# ESC_BOARD.net
KiCad netlist of a schematic drawn in EAGLE
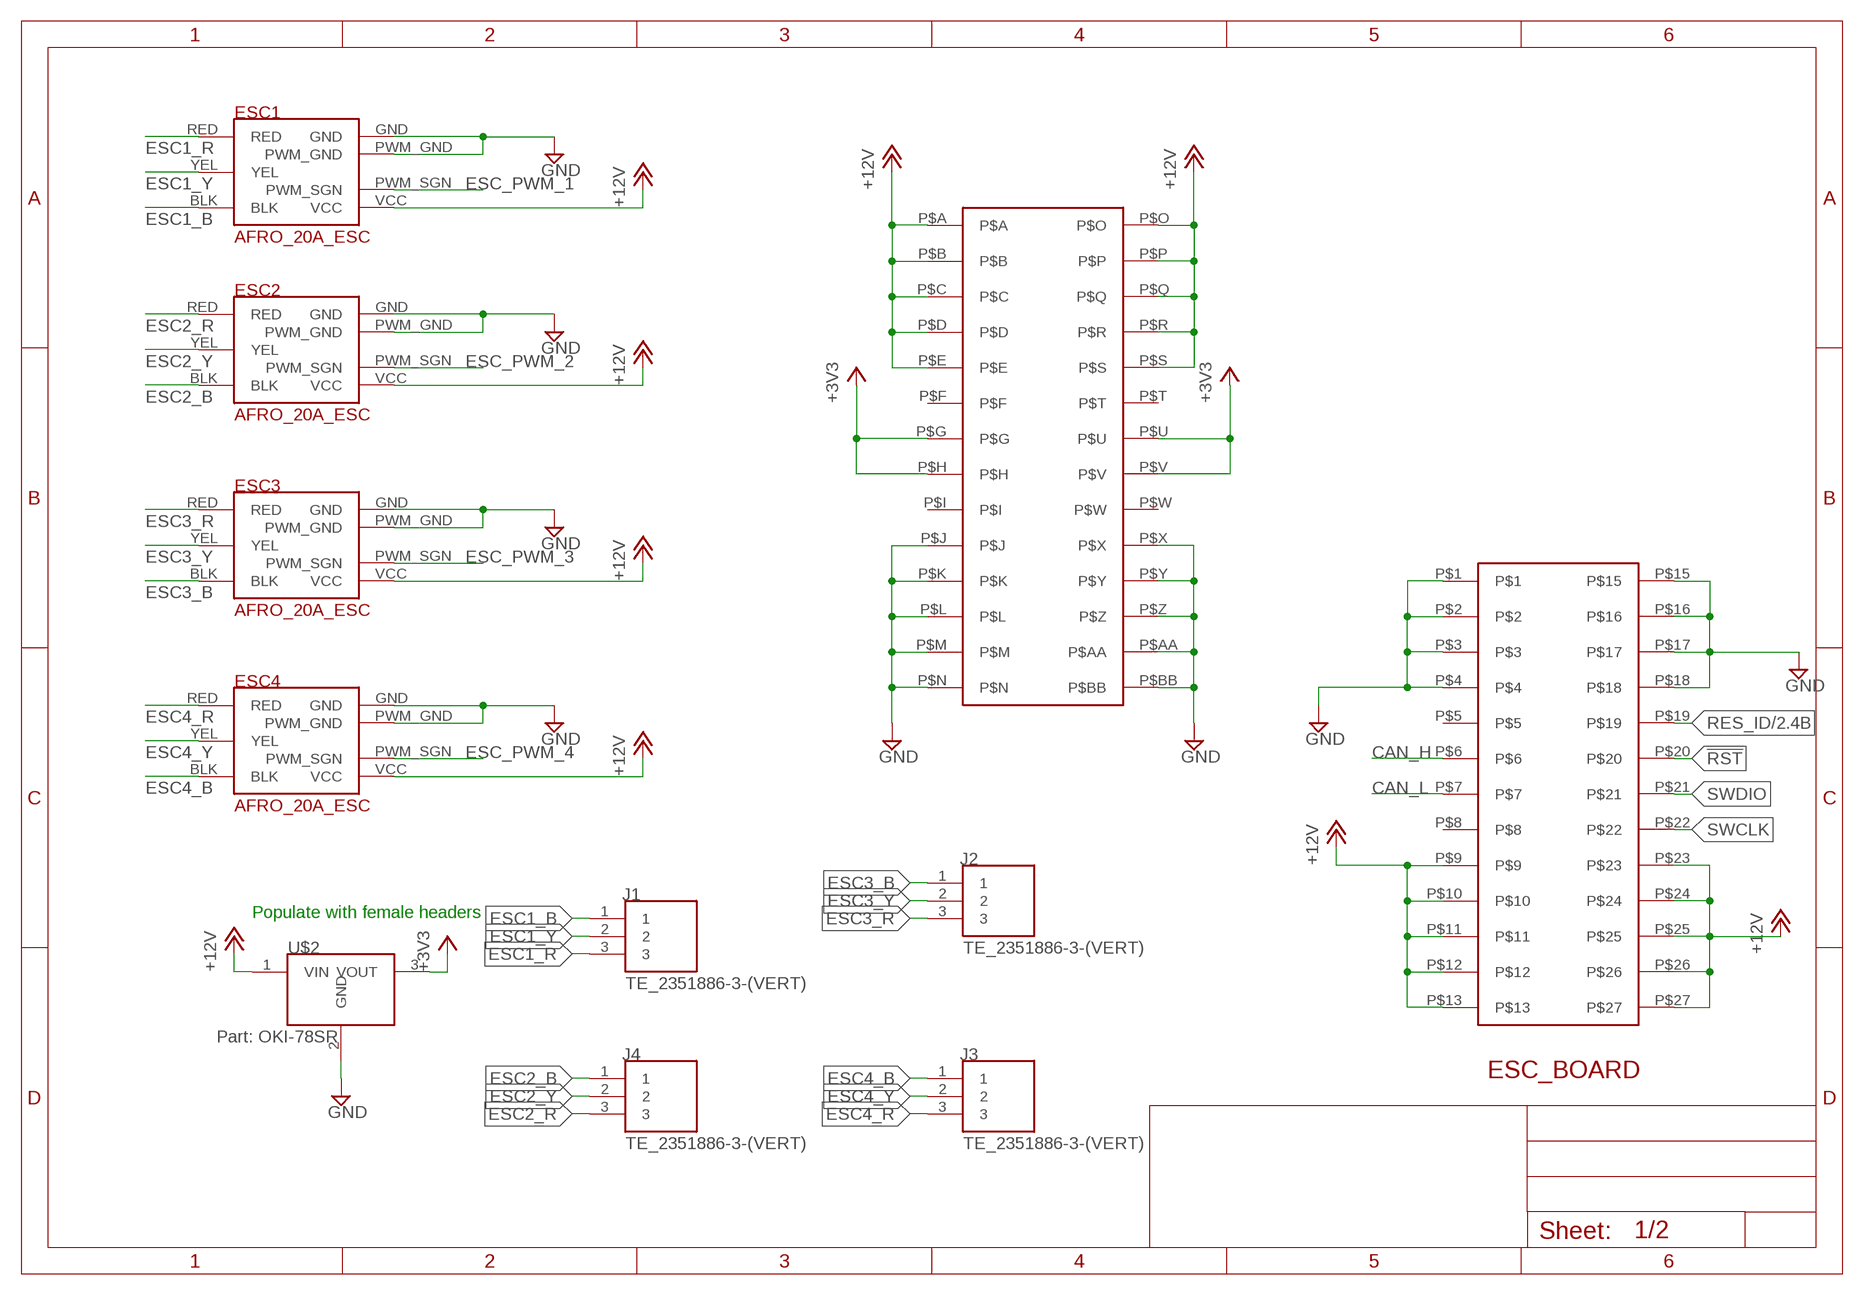
[diagram p0: schematic, sheet 1]
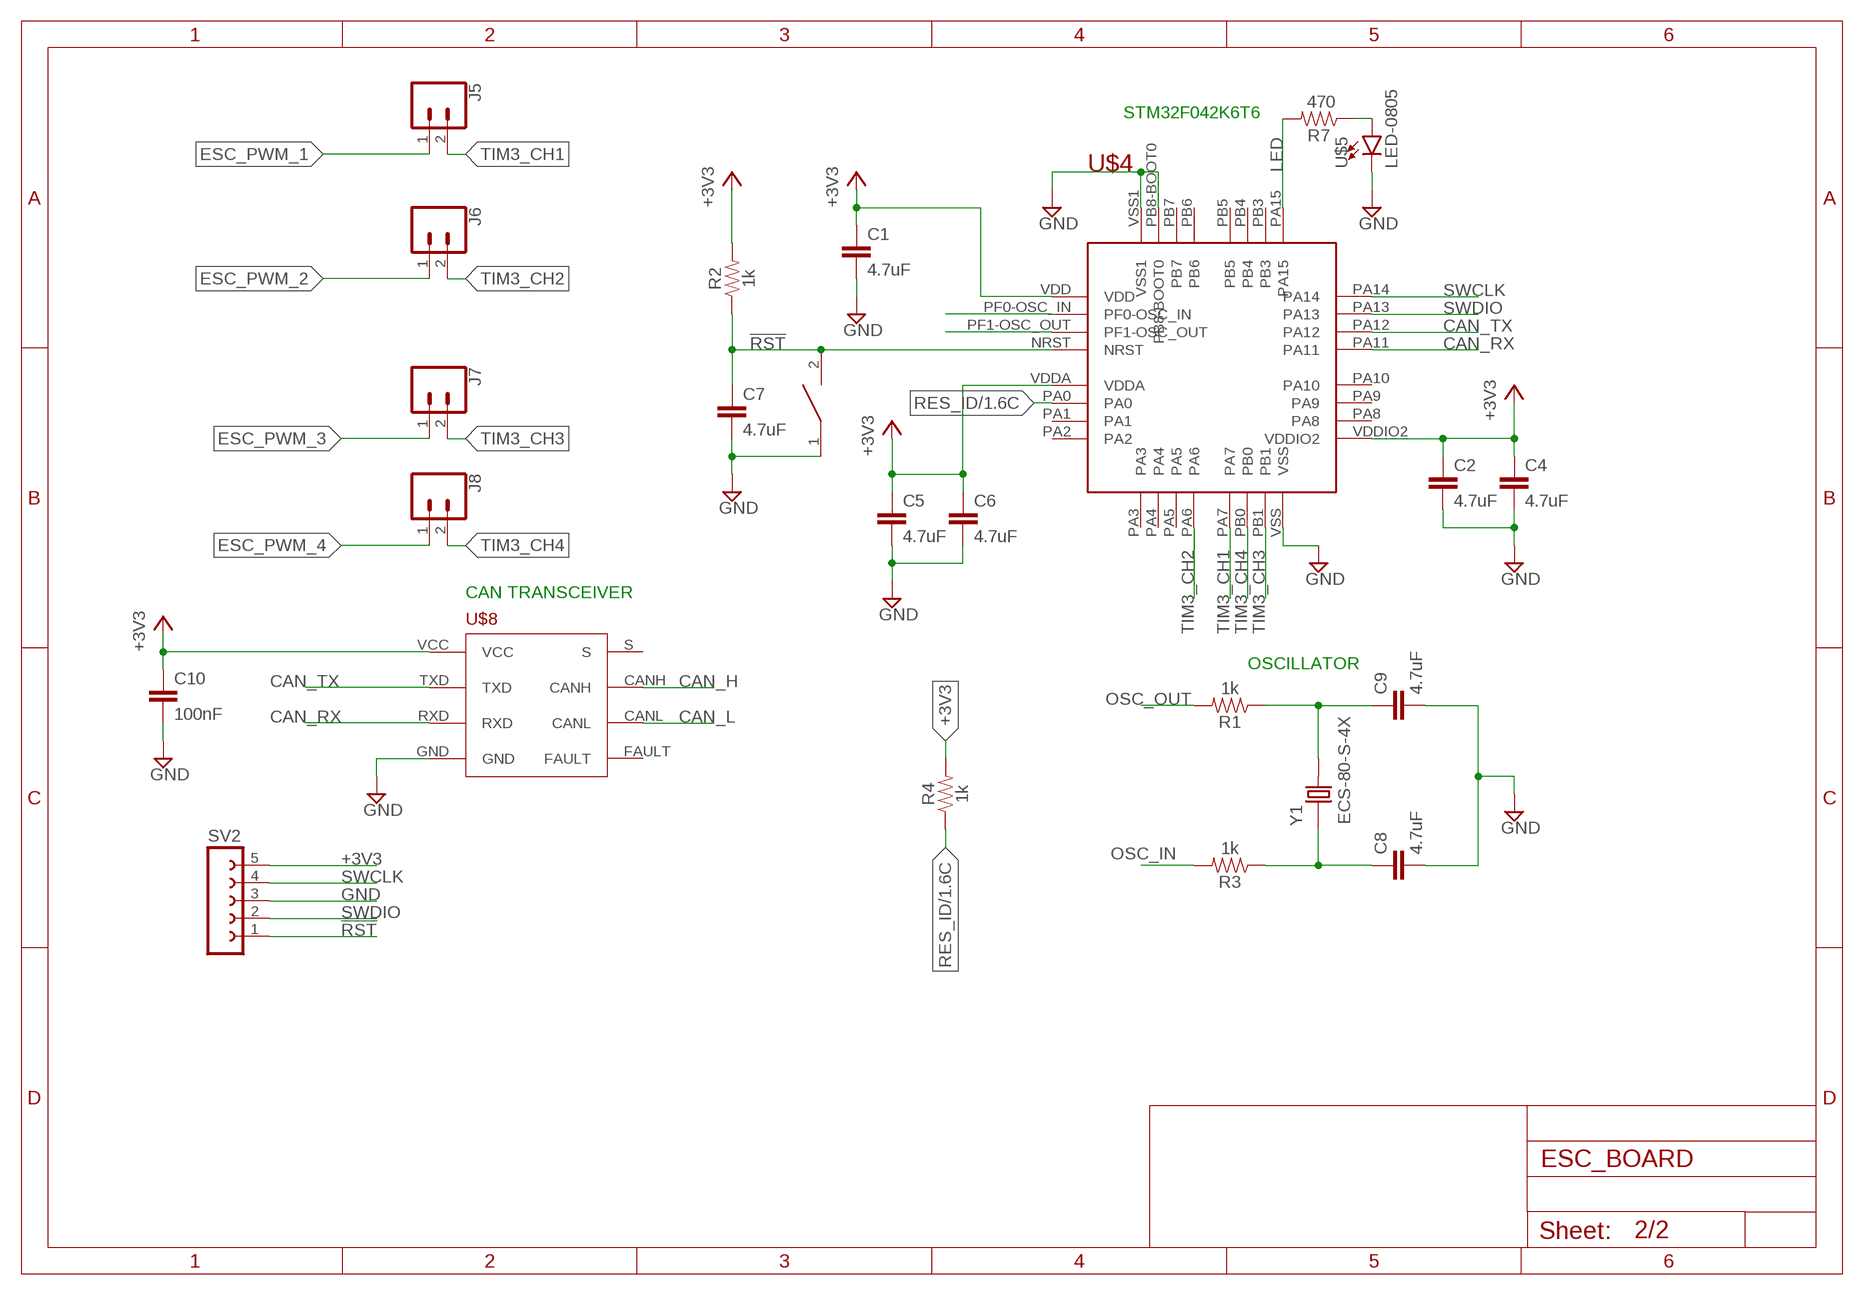
[diagram p1: schematic, sheet 2]

(export (version "E")
  (design (tool "Eeschema 10.0.6"))
  (components
    (comp (ref "C1")
      (value "4.7uF")
      (footprint "eagle-import:0603")
      (libsource (lib "eagle-import") (part "4.7UF0603"))
    )
    (comp (ref "C2")
      (value "4.7uF")
      (footprint "eagle-import:0603")
      (libsource (lib "eagle-import") (part "4.7UF0603"))
    )
    (comp (ref "C4")
      (value "4.7uF")
      (footprint "eagle-import:0603")
      (libsource (lib "eagle-import") (part "4.7UF0603"))
    )
    (comp (ref "C5")
      (value "4.7uF")
      (footprint "eagle-import:0603")
      (libsource (lib "eagle-import") (part "4.7UF0603"))
    )
    (comp (ref "C6")
      (value "4.7uF")
      (footprint "eagle-import:0603")
      (libsource (lib "eagle-import") (part "4.7UF0603"))
    )
    (comp (ref "C7")
      (value "4.7uF")
      (footprint "eagle-import:0603")
      (libsource (lib "eagle-import") (part "4.7UF0603"))
    )
    (comp (ref "C8")
      (value "4.7uF")
      (footprint "eagle-import:0603")
      (libsource (lib "eagle-import") (part "4.7UF0603"))
    )
    (comp (ref "C9")
      (value "4.7uF")
      (footprint "eagle-import:0603")
      (libsource (lib "eagle-import") (part "4.7UF0603"))
    )
    (comp (ref "C10")
      (value "100nF")
      (footprint "eagle-import:0603")
      (libsource (lib "eagle-import") (part "4.7UF0603"))
    )
    (comp (ref "J5")
      (value "CONN_02")
      (footprint "eagle-import:1X02")
      (libsource (lib "eagle-import") (part "CONN_02"))
    )
    (comp (ref "J6")
      (value "CONN_02")
      (footprint "eagle-import:1X02")
      (libsource (lib "eagle-import") (part "CONN_02"))
    )
    (comp (ref "J7")
      (value "CONN_02")
      (footprint "eagle-import:1X02")
      (libsource (lib "eagle-import") (part "CONN_02"))
    )
    (comp (ref "J8")
      (value "CONN_02")
      (footprint "eagle-import:1X02")
      (libsource (lib "eagle-import") (part "CONN_02"))
    )
    (comp (ref "R1")
      (value "1k")
      (footprint "eagle-import:0603")
      (libsource (lib "eagle-import") (part "1KOHM-0603-1/10W-1%"))
    )
    (comp (ref "R2")
      (value "1k")
      (footprint "eagle-import:0603")
      (libsource (lib "eagle-import") (part "1KOHM-0603-1/10W-1%"))
    )
    (comp (ref "R3")
      (value "1k")
      (footprint "eagle-import:0603")
      (libsource (lib "eagle-import") (part "1KOHM-0603-1/10W-1%"))
    )
    (comp (ref "R4")
      (value "1k")
      (footprint "eagle-import:0603")
      (libsource (lib "eagle-import") (part "1KOHM-0603-1/10W-1%"))
    )
    (comp (ref "R7")
      (value "470")
      (footprint "eagle-import:0603")
      (libsource (lib "eagle-import") (part "RESISTOR0603"))
    )
    (comp (ref "SV2")
      (value "FE05-1")
      (footprint "eagle-import:FE05-1")
      (libsource (lib "eagle-import") (part "FE05-1"))
    )
    (comp (ref "U$3")
      (value "DISCRETECOMPONENTS_SWITCH")
      (footprint "eagle-import:DISCRETECOMPONENTS_SW_2512")
      (libsource (lib "eagle-import") (part "DISCRETECOMPONENTS_SWITCH"))
    )
    (comp (ref "U$4")
      (value "STM32F042K6T6")
      (footprint "eagle-import:STM32F042K6T6")
      (libsource (lib "eagle-import") (part "STM32F042K6T6"))
    )
    (comp (ref "U$5")
      (value "LED-0805")
      (footprint "eagle-import:0805")
      (libsource (lib "eagle-import") (part "LED-0805"))
    )
    (comp (ref "U$8")
      (value "TCAN337D")
      (footprint "eagle-import:TCAN337D")
      (libsource (lib "eagle-import") (part "TCAN337D"))
    )
    (comp (ref "Y1")
      (value "ECS-80-S-4X")
      (footprint "eagle-import:XTAL_ECS-80-S-4X")
      (fields (field (name "DIGI-KEY_PART_NUMBER") "X1057-ND") (field (name "MF") "ECS International"))
      (libsource (lib "eagle-import") (part "ECS-80-S-4X"))
    )
    (comp (ref "ESC1")
      (value "AFRO_20A_ESC")
      (footprint "eagle-import:AFRO_20A_ESC")
      (libsource (lib "eagle-import") (part "AFRO_20A_ESC"))
    )
    (comp (ref "ESC2")
      (value "AFRO_20A_ESC")
      (footprint "eagle-import:AFRO_20A_ESC")
      (libsource (lib "eagle-import") (part "AFRO_20A_ESC"))
    )
    (comp (ref "ESC3")
      (value "AFRO_20A_ESC")
      (footprint "eagle-import:AFRO_20A_ESC")
      (libsource (lib "eagle-import") (part "AFRO_20A_ESC"))
    )
    (comp (ref "ESC4")
      (value "AFRO_20A_ESC")
      (footprint "eagle-import:AFRO_20A_ESC")
      (libsource (lib "eagle-import") (part "AFRO_20A_ESC"))
    )
    (comp (ref "J1")
      (value "TE_2351886-3-(VERT)")
      (footprint "eagle-import:TE_2351886-3-(VERT)")
      (libsource (lib "eagle-import") (part "TE_2351886-3-(VERT)"))
    )
    (comp (ref "J2")
      (value "TE_2351886-3-(VERT)")
      (footprint "eagle-import:TE_2351886-3-(VERT)")
      (libsource (lib "eagle-import") (part "TE_2351886-3-(VERT)"))
    )
    (comp (ref "J3")
      (value "TE_2351886-3-(VERT)")
      (footprint "eagle-import:TE_2351886-3-(VERT)")
      (libsource (lib "eagle-import") (part "TE_2351886-3-(VERT)"))
    )
    (comp (ref "J4")
      (value "TE_2351886-3-(VERT)")
      (footprint "eagle-import:TE_2351886-3-(VERT)")
      (libsource (lib "eagle-import") (part "TE_2351886-3-(VERT)"))
    )
    (comp (ref "U$2")
      (value "MURATA-DC-DC")
      (footprint "eagle-import:MURATA-DC-DC")
      (libsource (lib "eagle-import") (part "MURATA-DC-DC"))
    )
    (comp (ref "U$6")
      (value "ESC2BACKPLANE")
      (footprint "eagle-import:ESC2BACKPLANE_WHOLE")
      (libsource (lib "eagle-import") (part "ESC2BACKPLANE"))
    )
  )
  (nets
    (net (code "1") (name "+3V3") (class "Default")
      (node (ref "C1") (pin "1") (pinfunction "1_1") (pintype "passive"))
      (node (ref "C10") (pin "1") (pinfunction "1_1") (pintype "passive"))
      (node (ref "C2") (pin "1") (pinfunction "1_1") (pintype "passive"))
      (node (ref "C4") (pin "1") (pinfunction "1_1") (pintype "passive"))
      (node (ref "C5") (pin "1") (pinfunction "1_1") (pintype "passive"))
      (node (ref "C6") (pin "1") (pinfunction "1_1") (pintype "passive"))
      (node (ref "R2") (pin "2") (pinfunction "2_2") (pintype "passive"))
      (node (ref "R4") (pin "2") (pinfunction "2_2") (pintype "passive"))
      (node (ref "SV2") (pin "5") (pinfunction "5_5") (pintype "passive"))
      (node (ref "U$2") (pin "3") (pinfunction "VOUT_3") (pintype "bidirectional"))
      (node (ref "U$4") (pin "VDD") (pinfunction "VDD_VDD") (pintype "bidirectional"))
      (node (ref "U$4") (pin "VDDA") (pinfunction "VDDA_VDDA") (pintype "bidirectional"))
      (node (ref "U$4") (pin "VDDIO2") (pinfunction "VDDIO2_VDDIO2") (pintype "bidirectional"))
      (node (ref "U$6") (pin "P$G") (pinfunction "P$G_P$G") (pintype "bidirectional"))
      (node (ref "U$6") (pin "P$H") (pinfunction "P$H_P$H") (pintype "bidirectional"))
      (node (ref "U$6") (pin "P$U") (pinfunction "P$U_P$U") (pintype "bidirectional"))
      (node (ref "U$6") (pin "P$V") (pinfunction "P$V_P$V") (pintype "bidirectional"))
      (node (ref "U$8") (pin "VCC") (pinfunction "VCC_VCC") (pintype "bidirectional"))
    )
    (net (code "2") (name "+12V") (class "Default")
      (node (ref "ESC1") (pin "VCC") (pinfunction "VCC_VCC") (pintype "bidirectional"))
      (node (ref "ESC2") (pin "VCC") (pinfunction "VCC_VCC") (pintype "bidirectional"))
      (node (ref "ESC3") (pin "VCC") (pinfunction "VCC_VCC") (pintype "bidirectional"))
      (node (ref "ESC4") (pin "VCC") (pinfunction "VCC_VCC") (pintype "bidirectional"))
      (node (ref "U$2") (pin "1") (pinfunction "VIN_1") (pintype "bidirectional"))
      (node (ref "U$6") (pin "P$10") (pinfunction "P$10_P$10") (pintype "bidirectional"))
      (node (ref "U$6") (pin "P$11") (pinfunction "P$11_P$11") (pintype "bidirectional"))
      (node (ref "U$6") (pin "P$12") (pinfunction "P$12_P$12") (pintype "bidirectional"))
      (node (ref "U$6") (pin "P$13") (pinfunction "P$13_P$13") (pintype "bidirectional"))
      (node (ref "U$6") (pin "P$23") (pinfunction "P$23_P$23") (pintype "bidirectional"))
      (node (ref "U$6") (pin "P$24") (pinfunction "P$24_P$24") (pintype "bidirectional"))
      (node (ref "U$6") (pin "P$25") (pinfunction "P$25_P$25") (pintype "bidirectional"))
      (node (ref "U$6") (pin "P$26") (pinfunction "P$26_P$26") (pintype "bidirectional"))
      (node (ref "U$6") (pin "P$27") (pinfunction "P$27_P$27") (pintype "bidirectional"))
      (node (ref "U$6") (pin "P$9") (pinfunction "P$9_P$9") (pintype "bidirectional"))
      (node (ref "U$6") (pin "P$A") (pinfunction "P$A_P$A") (pintype "bidirectional"))
      (node (ref "U$6") (pin "P$B") (pinfunction "P$B_P$B") (pintype "bidirectional"))
      (node (ref "U$6") (pin "P$C") (pinfunction "P$C_P$C") (pintype "bidirectional"))
      (node (ref "U$6") (pin "P$D") (pinfunction "P$D_P$D") (pintype "bidirectional"))
      (node (ref "U$6") (pin "P$E") (pinfunction "P$E_P$E") (pintype "bidirectional"))
      (node (ref "U$6") (pin "P$O") (pinfunction "P$O_P$O") (pintype "bidirectional"))
      (node (ref "U$6") (pin "P$P") (pinfunction "P$P_P$P") (pintype "bidirectional"))
      (node (ref "U$6") (pin "P$Q") (pinfunction "P$Q_P$Q") (pintype "bidirectional"))
      (node (ref "U$6") (pin "P$R") (pinfunction "P$R_P$R") (pintype "bidirectional"))
      (node (ref "U$6") (pin "P$S") (pinfunction "P$S_P$S") (pintype "bidirectional"))
    )
    (net (code "3") (name "CAN_H") (class "Default")
      (node (ref "U$6") (pin "P$6") (pinfunction "P$6_P$6") (pintype "bidirectional"))
      (node (ref "U$8") (pin "CANH") (pinfunction "CANH_CANH") (pintype "bidirectional"))
    )
    (net (code "4") (name "CAN_L") (class "Default")
      (node (ref "U$6") (pin "P$7") (pinfunction "P$7_P$7") (pintype "bidirectional"))
      (node (ref "U$8") (pin "CANL") (pinfunction "CANL_CANL") (pintype "bidirectional"))
    )
    (net (code "5") (name "CAN_RX") (class "Default")
      (node (ref "U$4") (pin "PA11") (pinfunction "PA11_PA11") (pintype "bidirectional"))
      (node (ref "U$8") (pin "RXD") (pinfunction "RXD_RXD") (pintype "bidirectional"))
    )
    (net (code "6") (name "CAN_TX") (class "Default")
      (node (ref "U$4") (pin "PA12") (pinfunction "PA12_PA12") (pintype "bidirectional"))
      (node (ref "U$8") (pin "TXD") (pinfunction "TXD_TXD") (pintype "bidirectional"))
    )
    (net (code "7") (name "ESC1_B") (class "Default")
      (node (ref "ESC1") (pin "BLK") (pinfunction "BLK_BLK") (pintype "bidirectional"))
      (node (ref "J1") (pin "1") (pinfunction "1_1") (pintype "passive"))
    )
    (net (code "8") (name "ESC1_R") (class "Default")
      (node (ref "ESC1") (pin "RED") (pinfunction "RED_RED") (pintype "bidirectional"))
      (node (ref "J1") (pin "3") (pinfunction "3_3") (pintype "passive"))
    )
    (net (code "9") (name "ESC1_Y") (class "Default")
      (node (ref "ESC1") (pin "YEL") (pinfunction "YEL_YEL") (pintype "bidirectional"))
      (node (ref "J1") (pin "2") (pinfunction "2_2") (pintype "passive"))
    )
    (net (code "10") (name "ESC2_B") (class "Default")
      (node (ref "ESC2") (pin "BLK") (pinfunction "BLK_BLK") (pintype "bidirectional"))
      (node (ref "J4") (pin "1") (pinfunction "1_1") (pintype "passive"))
    )
    (net (code "11") (name "ESC2_R") (class "Default")
      (node (ref "ESC2") (pin "RED") (pinfunction "RED_RED") (pintype "bidirectional"))
      (node (ref "J4") (pin "3") (pinfunction "3_3") (pintype "passive"))
    )
    (net (code "12") (name "ESC2_Y") (class "Default")
      (node (ref "ESC2") (pin "YEL") (pinfunction "YEL_YEL") (pintype "bidirectional"))
      (node (ref "J4") (pin "2") (pinfunction "2_2") (pintype "passive"))
    )
    (net (code "13") (name "ESC3_B") (class "Default")
      (node (ref "ESC3") (pin "BLK") (pinfunction "BLK_BLK") (pintype "bidirectional"))
      (node (ref "J2") (pin "1") (pinfunction "1_1") (pintype "passive"))
    )
    (net (code "14") (name "ESC3_R") (class "Default")
      (node (ref "ESC3") (pin "RED") (pinfunction "RED_RED") (pintype "bidirectional"))
      (node (ref "J2") (pin "3") (pinfunction "3_3") (pintype "passive"))
    )
    (net (code "15") (name "ESC3_Y") (class "Default")
      (node (ref "ESC3") (pin "YEL") (pinfunction "YEL_YEL") (pintype "bidirectional"))
      (node (ref "J2") (pin "2") (pinfunction "2_2") (pintype "passive"))
    )
    (net (code "16") (name "ESC4_B") (class "Default")
      (node (ref "ESC4") (pin "BLK") (pinfunction "BLK_BLK") (pintype "bidirectional"))
      (node (ref "J3") (pin "1") (pinfunction "1_1") (pintype "passive"))
    )
    (net (code "17") (name "ESC4_R") (class "Default")
      (node (ref "ESC4") (pin "RED") (pinfunction "RED_RED") (pintype "bidirectional"))
      (node (ref "J3") (pin "3") (pinfunction "3_3") (pintype "passive"))
    )
    (net (code "18") (name "ESC4_Y") (class "Default")
      (node (ref "ESC4") (pin "YEL") (pinfunction "YEL_YEL") (pintype "bidirectional"))
      (node (ref "J3") (pin "2") (pinfunction "2_2") (pintype "passive"))
    )
    (net (code "19") (name "ESC_PWM_1") (class "Default")
      (node (ref "ESC1") (pin "PWM_SGN") (pinfunction "PWM_SGN_PWM_SGN") (pintype "bidirectional"))
      (node (ref "J5") (pin "1") (pinfunction "1_1") (pintype "passive"))
    )
    (net (code "20") (name "ESC_PWM_2") (class "Default")
      (node (ref "ESC2") (pin "PWM_SGN") (pinfunction "PWM_SGN_PWM_SGN") (pintype "bidirectional"))
      (node (ref "J6") (pin "1") (pinfunction "1_1") (pintype "passive"))
    )
    (net (code "21") (name "ESC_PWM_3") (class "Default")
      (node (ref "ESC3") (pin "PWM_SGN") (pinfunction "PWM_SGN_PWM_SGN") (pintype "bidirectional"))
      (node (ref "J7") (pin "1") (pinfunction "1_1") (pintype "passive"))
    )
    (net (code "22") (name "ESC_PWM_4") (class "Default")
      (node (ref "ESC4") (pin "PWM_SGN") (pinfunction "PWM_SGN_PWM_SGN") (pintype "bidirectional"))
      (node (ref "J8") (pin "1") (pinfunction "1_1") (pintype "passive"))
    )
    (net (code "23") (name "GND") (class "Default")
      (node (ref "C1") (pin "2") (pinfunction "2_2") (pintype "passive"))
      (node (ref "C10") (pin "2") (pinfunction "2_2") (pintype "passive"))
      (node (ref "C2") (pin "2") (pinfunction "2_2") (pintype "passive"))
      (node (ref "C4") (pin "2") (pinfunction "2_2") (pintype "passive"))
      (node (ref "C5") (pin "2") (pinfunction "2_2") (pintype "passive"))
      (node (ref "C6") (pin "2") (pinfunction "2_2") (pintype "passive"))
      (node (ref "C7") (pin "2") (pinfunction "2_2") (pintype "passive"))
      (node (ref "C8") (pin "2") (pinfunction "2_2") (pintype "passive"))
      (node (ref "C9") (pin "2") (pinfunction "2_2") (pintype "passive"))
      (node (ref "ESC1") (pin "GND") (pinfunction "GND_GND") (pintype "bidirectional"))
      (node (ref "ESC1") (pin "PWM_GND") (pinfunction "PWM_GND_PWM_GND") (pintype "bidirectional"))
      (node (ref "ESC2") (pin "GND") (pinfunction "GND_GND") (pintype "bidirectional"))
      (node (ref "ESC2") (pin "PWM_GND") (pinfunction "PWM_GND_PWM_GND") (pintype "bidirectional"))
      (node (ref "ESC3") (pin "GND") (pinfunction "GND_GND") (pintype "bidirectional"))
      (node (ref "ESC3") (pin "PWM_GND") (pinfunction "PWM_GND_PWM_GND") (pintype "bidirectional"))
      (node (ref "ESC4") (pin "GND") (pinfunction "GND_GND") (pintype "bidirectional"))
      (node (ref "ESC4") (pin "PWM_GND") (pinfunction "PWM_GND_PWM_GND") (pintype "bidirectional"))
      (node (ref "SV2") (pin "3") (pinfunction "3_3") (pintype "passive"))
      (node (ref "U$2") (pin "2") (pinfunction "GND_2") (pintype "bidirectional"))
      (node (ref "U$3") (pin "1") (pinfunction "P$1_1") (pintype "bidirectional"))
      (node (ref "U$4") (pin "PB8-BOOT0") (pinfunction "PB8-BOOT0_PB8-BOOT0") (pintype "bidirectional"))
      (node (ref "U$4") (pin "VSS") (pinfunction "VSS_VSS") (pintype "bidirectional"))
      (node (ref "U$4") (pin "VSS1") (pinfunction "VSS1_VSS1") (pintype "bidirectional"))
      (node (ref "U$5") (pin "C") (pinfunction "C_C") (pintype "passive"))
      (node (ref "U$6") (pin "P$1") (pinfunction "P$1_P$1") (pintype "bidirectional"))
      (node (ref "U$6") (pin "P$15") (pinfunction "P$15_P$15") (pintype "bidirectional"))
      (node (ref "U$6") (pin "P$16") (pinfunction "P$16_P$16") (pintype "bidirectional"))
      (node (ref "U$6") (pin "P$17") (pinfunction "P$17_P$17") (pintype "bidirectional"))
      (node (ref "U$6") (pin "P$18") (pinfunction "P$18_P$18") (pintype "bidirectional"))
      (node (ref "U$6") (pin "P$2") (pinfunction "P$2_P$2") (pintype "bidirectional"))
      (node (ref "U$6") (pin "P$3") (pinfunction "P$3_P$3") (pintype "bidirectional"))
      (node (ref "U$6") (pin "P$4") (pinfunction "P$4_P$4") (pintype "bidirectional"))
      (node (ref "U$6") (pin "P$AA") (pinfunction "P$AA_P$AA") (pintype "bidirectional"))
      (node (ref "U$6") (pin "P$BB") (pinfunction "P$BB_P$BB") (pintype "bidirectional"))
      (node (ref "U$6") (pin "P$J") (pinfunction "P$J_P$J") (pintype "bidirectional"))
      (node (ref "U$6") (pin "P$K") (pinfunction "P$K_P$K") (pintype "bidirectional"))
      (node (ref "U$6") (pin "P$L") (pinfunction "P$L_P$L") (pintype "bidirectional"))
      (node (ref "U$6") (pin "P$M") (pinfunction "P$M_P$M") (pintype "bidirectional"))
      (node (ref "U$6") (pin "P$N") (pinfunction "P$N_P$N") (pintype "bidirectional"))
      (node (ref "U$6") (pin "P$X") (pinfunction "P$X_P$X") (pintype "bidirectional"))
      (node (ref "U$6") (pin "P$Y") (pinfunction "P$Y_P$Y") (pintype "bidirectional"))
      (node (ref "U$6") (pin "P$Z") (pinfunction "P$Z_P$Z") (pintype "bidirectional"))
      (node (ref "U$8") (pin "GND") (pinfunction "GND_GND") (pintype "bidirectional"))
    )
    (net (code "24") (name "LED") (class "Default")
      (node (ref "R7") (pin "2") (pinfunction "2_2") (pintype "passive"))
      (node (ref "U$4") (pin "PA15") (pinfunction "PA15_PA15") (pintype "bidirectional"))
    )
    (net (code "25") (name "Net-(C8-Pad1)") (class "Default")
      (node (ref "C8") (pin "1") (pinfunction "1_1") (pintype "passive"))
      (node (ref "R3") (pin "1") (pinfunction "1_1") (pintype "passive"))
      (node (ref "Y1") (pin "1") (pinfunction "1_1") (pintype "passive"))
    )
    (net (code "26") (name "Net-(C9-Pad1)") (class "Default")
      (node (ref "C9") (pin "1") (pinfunction "1_1") (pintype "passive"))
      (node (ref "R1") (pin "1") (pinfunction "1_1") (pintype "passive"))
      (node (ref "Y1") (pin "2") (pinfunction "2_2") (pintype "passive"))
    )
    (net (code "27") (name "Net-(R7-Pad1)") (class "Default")
      (node (ref "R7") (pin "1") (pinfunction "1_1") (pintype "passive"))
      (node (ref "U$5") (pin "A") (pinfunction "A_A") (pintype "passive"))
    )
    (net (code "28") (name "OSC_IN") (class "Default")
      (node (ref "R3") (pin "2") (pinfunction "2_2") (pintype "passive"))
      (node (ref "U$4") (pin "PF0-OSC_IN") (pinfunction "PF0-OSC_IN_PF0-OSC_IN") (pintype "bidirectional"))
    )
    (net (code "29") (name "OSC_OUT") (class "Default")
      (node (ref "R1") (pin "2") (pinfunction "2_2") (pintype "passive"))
      (node (ref "U$4") (pin "PF1-OSC_OUT") (pinfunction "PF1-OSC_OUT_PF1-OSC_OUT") (pintype "bidirectional"))
    )
    (net (code "30") (name "RES_ID") (class "Default")
      (node (ref "R4") (pin "1") (pinfunction "1_1") (pintype "passive"))
      (node (ref "U$4") (pin "PA0") (pinfunction "PA0_PA0") (pintype "bidirectional"))
      (node (ref "U$6") (pin "P$19") (pinfunction "P$19_P$19") (pintype "bidirectional"))
    )
    (net (code "31") (name "SWCLK") (class "Default")
      (node (ref "SV2") (pin "4") (pinfunction "4_4") (pintype "passive"))
      (node (ref "U$4") (pin "PA14") (pinfunction "PA14_PA14") (pintype "bidirectional"))
      (node (ref "U$6") (pin "P$22") (pinfunction "P$22_P$22") (pintype "bidirectional"))
    )
    (net (code "32") (name "SWDIO") (class "Default")
      (node (ref "SV2") (pin "2") (pinfunction "2_2") (pintype "passive"))
      (node (ref "U$4") (pin "PA13") (pinfunction "PA13_PA13") (pintype "bidirectional"))
      (node (ref "U$6") (pin "P$21") (pinfunction "P$21_P$21") (pintype "bidirectional"))
    )
    (net (code "33") (name "TIM3_CH1") (class "Default")
      (node (ref "J5") (pin "2") (pinfunction "2_2") (pintype "passive"))
      (node (ref "U$4") (pin "PA7") (pinfunction "PA7_PA7") (pintype "bidirectional"))
    )
    (net (code "34") (name "TIM3_CH2") (class "Default")
      (node (ref "J6") (pin "2") (pinfunction "2_2") (pintype "passive"))
      (node (ref "U$4") (pin "PA6") (pinfunction "PA6_PA6") (pintype "bidirectional"))
    )
    (net (code "35") (name "TIM3_CH3") (class "Default")
      (node (ref "J7") (pin "2") (pinfunction "2_2") (pintype "passive"))
      (node (ref "U$4") (pin "PB1") (pinfunction "PB1_PB1") (pintype "bidirectional"))
    )
    (net (code "36") (name "TIM3_CH4") (class "Default")
      (node (ref "J8") (pin "2") (pinfunction "2_2") (pintype "passive"))
      (node (ref "U$4") (pin "PB0") (pinfunction "PB0_PB0") (pintype "bidirectional"))
    )
    (net (code "37") (name "unconnected-(U$4-PadPA1)") (class "Default")
      (node (ref "U$4") (pin "PA1") (pinfunction "PA1_PA1") (pintype "bidirectional"))
    )
    (net (code "38") (name "unconnected-(U$4-PadPA2)") (class "Default")
      (node (ref "U$4") (pin "PA2") (pinfunction "PA2_PA2") (pintype "bidirectional"))
    )
    (net (code "39") (name "unconnected-(U$4-PadPA3)") (class "Default")
      (node (ref "U$4") (pin "PA3") (pinfunction "PA3_PA3") (pintype "bidirectional"))
    )
    (net (code "40") (name "unconnected-(U$4-PadPA4)") (class "Default")
      (node (ref "U$4") (pin "PA4") (pinfunction "PA4_PA4") (pintype "bidirectional"))
    )
    (net (code "41") (name "unconnected-(U$4-PadPA5)") (class "Default")
      (node (ref "U$4") (pin "PA5") (pinfunction "PA5_PA5") (pintype "bidirectional"))
    )
    (net (code "42") (name "unconnected-(U$4-PadPA8)") (class "Default")
      (node (ref "U$4") (pin "PA8") (pinfunction "PA8_PA8") (pintype "bidirectional"))
    )
    (net (code "43") (name "unconnected-(U$4-PadPA9)") (class "Default")
      (node (ref "U$4") (pin "PA9") (pinfunction "PA9_PA9") (pintype "bidirectional"))
    )
    (net (code "44") (name "unconnected-(U$4-PadPA10)") (class "Default")
      (node (ref "U$4") (pin "PA10") (pinfunction "PA10_PA10") (pintype "bidirectional"))
    )
    (net (code "45") (name "unconnected-(U$4-PadPB3)") (class "Default")
      (node (ref "U$4") (pin "PB3") (pinfunction "PB3_PB3") (pintype "bidirectional"))
    )
    (net (code "46") (name "unconnected-(U$4-PadPB4)") (class "Default")
      (node (ref "U$4") (pin "PB4") (pinfunction "PB4_PB4") (pintype "bidirectional"))
    )
    (net (code "47") (name "unconnected-(U$4-PadPB5)") (class "Default")
      (node (ref "U$4") (pin "PB5") (pinfunction "PB5_PB5") (pintype "bidirectional"))
    )
    (net (code "48") (name "unconnected-(U$4-PadPB6)") (class "Default")
      (node (ref "U$4") (pin "PB6") (pinfunction "PB6_PB6") (pintype "bidirectional"))
    )
    (net (code "49") (name "unconnected-(U$4-PadPB7)") (class "Default")
      (node (ref "U$4") (pin "PB7") (pinfunction "PB7_PB7") (pintype "bidirectional"))
    )
    (net (code "50") (name "unconnected-(U$6-PadP$5)") (class "Default")
      (node (ref "U$6") (pin "P$5") (pinfunction "P$5_P$5") (pintype "bidirectional"))
    )
    (net (code "51") (name "unconnected-(U$6-PadP$8)") (class "Default")
      (node (ref "U$6") (pin "P$8") (pinfunction "P$8_P$8") (pintype "bidirectional"))
    )
    (net (code "52") (name "unconnected-(U$6-PadP$F)") (class "Default")
      (node (ref "U$6") (pin "P$F") (pinfunction "P$F_P$F") (pintype "bidirectional"))
    )
    (net (code "53") (name "unconnected-(U$6-PadP$I)") (class "Default")
      (node (ref "U$6") (pin "P$I") (pinfunction "P$I_P$I") (pintype "bidirectional"))
    )
    (net (code "54") (name "unconnected-(U$6-PadP$T)") (class "Default")
      (node (ref "U$6") (pin "P$T") (pinfunction "P$T_P$T") (pintype "bidirectional"))
    )
    (net (code "55") (name "unconnected-(U$6-PadP$W)") (class "Default")
      (node (ref "U$6") (pin "P$W") (pinfunction "P$W_P$W") (pintype "bidirectional"))
    )
    (net (code "56") (name "unconnected-(U$8-PadFAULT)") (class "Default")
      (node (ref "U$8") (pin "FAULT") (pinfunction "FAULT_FAULT") (pintype "bidirectional"))
    )
    (net (code "57") (name "unconnected-(U$8-PadS)") (class "Default")
      (node (ref "U$8") (pin "S") (pinfunction "S_S") (pintype "bidirectional"))
    )
    (net (code "58") (name "~{RST}") (class "Default")
      (node (ref "C7") (pin "1") (pinfunction "1_1") (pintype "passive"))
      (node (ref "R2") (pin "1") (pinfunction "1_1") (pintype "passive"))
      (node (ref "SV2") (pin "1") (pinfunction "1_1") (pintype "passive"))
      (node (ref "U$3") (pin "2") (pinfunction "P$2_2") (pintype "bidirectional"))
      (node (ref "U$4") (pin "NRST") (pinfunction "NRST_NRST") (pintype "bidirectional"))
      (node (ref "U$6") (pin "P$20") (pinfunction "P$20_P$20") (pintype "bidirectional"))
    )
  )
)
